# PTMe-stop.net
KiCad netlist of a schematic drawn in Altium Designer
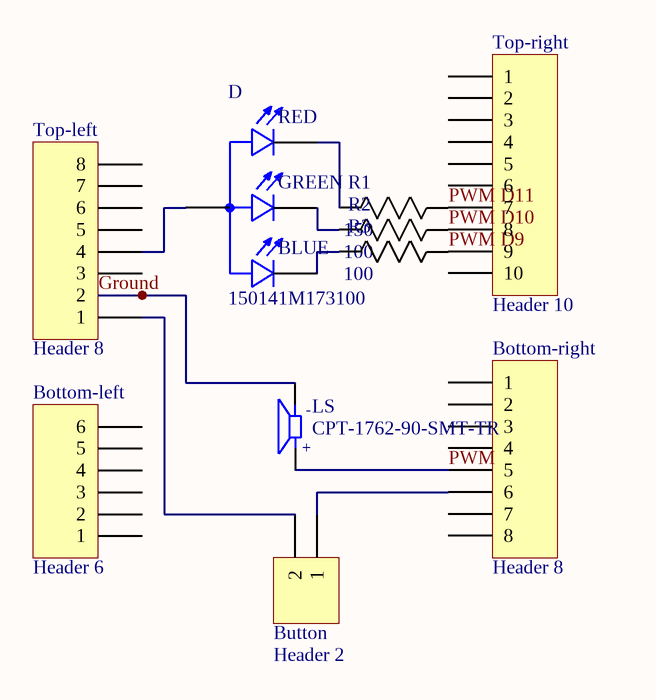
[diagram p0: PTMe-stop.SchDoc]

(export (version "E")
  (design (tool "Eeschema 10.0.6"))
  (components
    (comp (ref "Bottom-left")
      (value "Header 6")
      (footprint "HDR1X6")
      (description "Header, 6-Pin")
      (fields (field (name "PUBLISHER") "Altium Limited"))
      (libsource (lib "Miscellaneous Connectors") (part "Header 6"))
    )
    (comp (ref "Bottom-right")
      (value "Header 8")
      (footprint "HDR1X8")
      (description "Header, 8-Pin")
      (fields (field (name "PUBLISHER") "Altium Limited"))
      (libsource (lib "") (part "Header 8_1"))
    )
    (comp (ref "Button")
      (value "Header 2")
      (footprint "HDR1X2")
      (description "Header, 2-Pin")
      (fields (field (name "PUBLISHER") "Altium Limited"))
      (libsource (lib "Miscellaneous Connectors") (part "Header 2"))
    )
    (comp (ref "D")
      (value "150141M173100")
      (footprint "LED_150141M173100")
      (fields (field (name "MF") "Wurth Electronics"))
      (libsource (lib "150141M173100") (part "150141M173100"))
    )
    (comp (ref "LS")
      (value "CPT-1762-90-SMT-TR")
      (footprint "XDCR_CPT-1762-90-SMT-TR")
      (description "17 mm, 12 Vp-p, 90 dB, Surface Mount, Piezo Audio Transducer Buzzer")
      (fields (field (name "MF") "CUI Devices"))
      (libsource (lib "CPT-1762-90-SMT-TR") (part "CPT-1762-90-SMT-TR"))
    )
    (comp (ref "R1")
      (value "150")
      (footprint "0805")
      (description "RES SMD 150 OHM 5% 1/8W 0805")
      (fields (field (name "TOLERANCE") "5%"))
      (libsource (lib "AltiumLibraries") (part "RES 150.0 1/8W"))
    )
    (comp (ref "R2")
      (value "100")
      (footprint "0805")
      (description "RES SMD 100 OHM 5% 1/8W 0805")
      (fields (field (name "TOLERANCE") "5%"))
      (libsource (lib "AltiumLibraries") (part "RES 100.0 1/8W"))
    )
    (comp (ref "R3")
      (value "100")
      (footprint "0805")
      (description "RES SMD 100 OHM 5% 1/8W 0805")
      (fields (field (name "TOLERANCE") "5%"))
      (libsource (lib "") (part "RES 100.0 1/8W_1"))
    )
    (comp (ref "Top-left")
      (value "Header 8")
      (footprint "HDR1X8")
      (description "Header, 8-Pin")
      (fields (field (name "PUBLISHER") "Altium Limited"))
      (libsource (lib "Miscellaneous Connectors") (part "Header 8"))
    )
    (comp (ref "Top-right")
      (value "Header 10")
      (footprint "HDR1X10")
      (description "Header, 10-Pin")
      (fields (field (name "PUBLISHER") "Altium Limited"))
      (libsource (lib "Miscellaneous Connectors") (part "Header 10"))
    )
  )
  (nets
    (net (code "1") (name "/Ground") (class "Default")
      (node (ref "LS") (pin "N") (pinfunction "N_N") (pintype "passive"))
      (node (ref "Top-left") (pin "2") (pinfunction "2_2") (pintype "passive"))
    )
    (net (code "2") (name "/PWM") (class "Default")
      (node (ref "Bottom-right") (pin "5") (pinfunction "5_5") (pintype "passive"))
      (node (ref "LS") (pin "P") (pinfunction "P_P") (pintype "passive"))
    )
    (net (code "3") (name "/PWM D9") (class "Default")
      (node (ref "R3") (pin "1") (pinfunction "R1_1") (pintype "passive"))
      (node (ref "Top-right") (pin "9") (pinfunction "9_9") (pintype "passive"))
    )
    (net (code "4") (name "/PWM D10") (class "Default")
      (node (ref "R2") (pin "1") (pinfunction "R1_1") (pintype "passive"))
      (node (ref "Top-right") (pin "8") (pinfunction "8_8") (pintype "passive"))
    )
    (net (code "5") (name "/PWM D11") (class "Default")
      (node (ref "R1") (pin "1") (pinfunction "R1_1") (pintype "passive"))
      (node (ref "Top-right") (pin "7") (pinfunction "7_7") (pintype "passive"))
    )
    (net (code "6") (name "Net-(Bottom-right-Pad6)") (class "Default")
      (node (ref "Bottom-right") (pin "6") (pinfunction "6_6") (pintype "passive"))
      (node (ref "Button") (pin "1") (pinfunction "1_1") (pintype "passive"))
    )
    (net (code "7") (name "Net-(Button-Pad2)") (class "Default")
      (node (ref "Button") (pin "2") (pinfunction "2_2") (pintype "passive"))
      (node (ref "Top-left") (pin "1") (pinfunction "1_1") (pintype "passive"))
    )
    (net (code "8") (name "Net-(D-A)") (class "Default")
      (node (ref "D") (pin "1") (pinfunction "A_1") (pintype "passive"))
      (node (ref "Top-left") (pin "4") (pinfunction "4_4") (pintype "passive"))
    )
    (net (code "9") (name "Net-(D-B_C)") (class "Default")
      (node (ref "D") (pin "2") (pinfunction "B_C_2") (pintype "passive"))
      (node (ref "R3") (pin "2") (pinfunction "R2_2") (pintype "passive"))
    )
    (net (code "10") (name "Net-(D-G_C)") (class "Default")
      (node (ref "D") (pin "4") (pinfunction "G_C_4") (pintype "passive"))
      (node (ref "R2") (pin "2") (pinfunction "R2_2") (pintype "passive"))
    )
    (net (code "11") (name "Net-(D-R_C)") (class "Default")
      (node (ref "D") (pin "3") (pinfunction "R_C_3") (pintype "passive"))
      (node (ref "R1") (pin "2") (pinfunction "R2_2") (pintype "passive"))
    )
    (net (code "12") (name "unconnected-(Bottom-left-Pad1)") (class "Default")
      (node (ref "Bottom-left") (pin "1") (pinfunction "1_1") (pintype "passive"))
    )
    (net (code "13") (name "unconnected-(Bottom-left-Pad2)") (class "Default")
      (node (ref "Bottom-left") (pin "2") (pinfunction "2_2") (pintype "passive"))
    )
    (net (code "14") (name "unconnected-(Bottom-left-Pad3)") (class "Default")
      (node (ref "Bottom-left") (pin "3") (pinfunction "3_3") (pintype "passive"))
    )
    (net (code "15") (name "unconnected-(Bottom-left-Pad4)") (class "Default")
      (node (ref "Bottom-left") (pin "4") (pinfunction "4_4") (pintype "passive"))
    )
    (net (code "16") (name "unconnected-(Bottom-left-Pad5)") (class "Default")
      (node (ref "Bottom-left") (pin "5") (pinfunction "5_5") (pintype "passive"))
    )
    (net (code "17") (name "unconnected-(Bottom-left-Pad6)") (class "Default")
      (node (ref "Bottom-left") (pin "6") (pinfunction "6_6") (pintype "passive"))
    )
    (net (code "18") (name "unconnected-(Bottom-right-Pad1)") (class "Default")
      (node (ref "Bottom-right") (pin "1") (pinfunction "1_1") (pintype "passive"))
    )
    (net (code "19") (name "unconnected-(Bottom-right-Pad2)") (class "Default")
      (node (ref "Bottom-right") (pin "2") (pinfunction "2_2") (pintype "passive"))
    )
    (net (code "20") (name "unconnected-(Bottom-right-Pad3)") (class "Default")
      (node (ref "Bottom-right") (pin "3") (pinfunction "3_3") (pintype "passive"))
    )
    (net (code "21") (name "unconnected-(Bottom-right-Pad4)") (class "Default")
      (node (ref "Bottom-right") (pin "4") (pinfunction "4_4") (pintype "passive"))
    )
    (net (code "22") (name "unconnected-(Bottom-right-Pad7)") (class "Default")
      (node (ref "Bottom-right") (pin "7") (pinfunction "7_7") (pintype "passive"))
    )
    (net (code "23") (name "unconnected-(Bottom-right-Pad8)") (class "Default")
      (node (ref "Bottom-right") (pin "8") (pinfunction "8_8") (pintype "passive"))
    )
    (net (code "24") (name "unconnected-(Top-left-Pad3)") (class "Default")
      (node (ref "Top-left") (pin "3") (pinfunction "3_3") (pintype "passive"))
    )
    (net (code "25") (name "unconnected-(Top-left-Pad5)") (class "Default")
      (node (ref "Top-left") (pin "5") (pinfunction "5_5") (pintype "passive"))
    )
    (net (code "26") (name "unconnected-(Top-left-Pad6)") (class "Default")
      (node (ref "Top-left") (pin "6") (pinfunction "6_6") (pintype "passive"))
    )
    (net (code "27") (name "unconnected-(Top-left-Pad7)") (class "Default")
      (node (ref "Top-left") (pin "7") (pinfunction "7_7") (pintype "passive"))
    )
    (net (code "28") (name "unconnected-(Top-left-Pad8)") (class "Default")
      (node (ref "Top-left") (pin "8") (pinfunction "8_8") (pintype "passive"))
    )
    (net (code "29") (name "unconnected-(Top-right-Pad1)") (class "Default")
      (node (ref "Top-right") (pin "1") (pinfunction "1_1") (pintype "passive"))
    )
    (net (code "30") (name "unconnected-(Top-right-Pad2)") (class "Default")
      (node (ref "Top-right") (pin "2") (pinfunction "2_2") (pintype "passive"))
    )
    (net (code "31") (name "unconnected-(Top-right-Pad3)") (class "Default")
      (node (ref "Top-right") (pin "3") (pinfunction "3_3") (pintype "passive"))
    )
    (net (code "32") (name "unconnected-(Top-right-Pad4)") (class "Default")
      (node (ref "Top-right") (pin "4") (pinfunction "4_4") (pintype "passive"))
    )
    (net (code "33") (name "unconnected-(Top-right-Pad5)") (class "Default")
      (node (ref "Top-right") (pin "5") (pinfunction "5_5") (pintype "passive"))
    )
    (net (code "34") (name "unconnected-(Top-right-Pad6)") (class "Default")
      (node (ref "Top-right") (pin "6") (pinfunction "6_6") (pintype "passive"))
    )
    (net (code "35") (name "unconnected-(Top-right-Pad10)") (class "Default")
      (node (ref "Top-right") (pin "10") (pinfunction "10_10") (pintype "passive"))
    )
  )
)
